# Current_Meas.net
KiCad netlist of a schematic drawn in Altium Designer
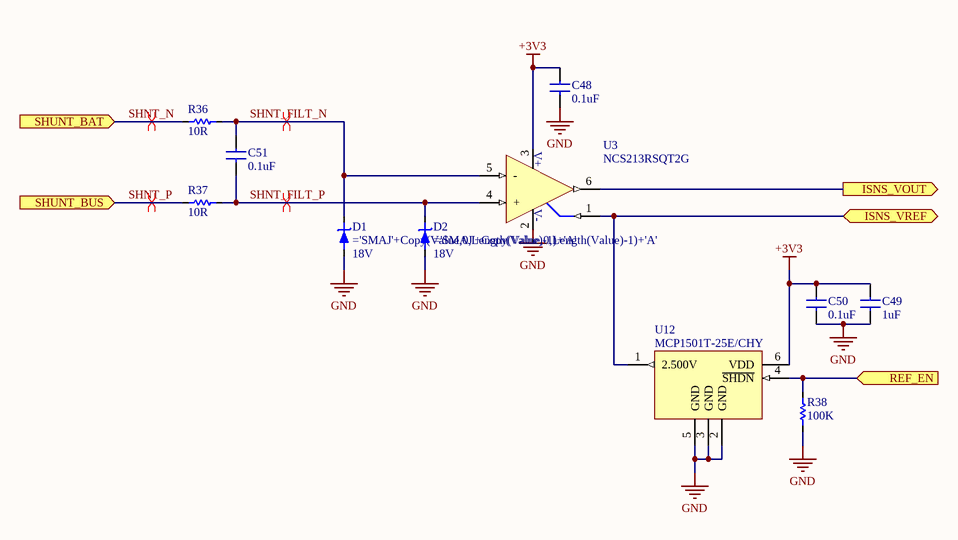
[diagram p0: Current_Meas.SchDoc]

(export (version "E")
  (design (tool "Eeschema 10.0.6"))
  (components
    (comp (ref "C48")
      (value "0.1uF")
      (footprint "0402_CAPACITOR")
      (description "CAP CERM 0.1uF 10% 16V 0402")
      (fields (field (name "VOLTAGE") "16V") (field (name "Comment") "CAP 0.1uF 16V X7R"))
      (libsource (lib "capacitor") (part "C_0402_0.1uF_16V_10%"))
    )
    (comp (ref "C49")
      (value "1uF")
      (footprint "0402_CAPACITOR")
      (description "CAP CERM 1uF 20% 6.3V 0402")
      (fields (field (name "VOLTAGE") "6.3V") (field (name "Comment") "CAP 1uF 6.3V X5R"))
      (libsource (lib "capacitor") (part "C_0402_1uF_6.3V_20%"))
    )
    (comp (ref "C50")
      (value "0.1uF")
      (footprint "0402_CAPACITOR")
      (description "CAP CERM 0.1uF 10% 16V 0402")
      (fields (field (name "VOLTAGE") "16V") (field (name "Comment") "CAP 0.1uF 16V X7R"))
      (libsource (lib "capacitor") (part "C_0402_0.1uF_16V_10%"))
    )
    (comp (ref "C51")
      (value "0.1uF")
      (footprint "0402_CAPACITOR")
      (description "CAP CERM 0.1uF 10% 16V 0402")
      (fields (field (name "VOLTAGE") "16V") (field (name "Comment") "CAP 0.1uF 16V X7R"))
      (libsource (lib "capacitor") (part "C_0402_0.1uF_16V_10%"))
    )
    (comp (ref "D1")
      (value "18V")
      (footprint "SMA")
      (description "SMA Unidirectional TVS Diode")
      (fields
        (field (name "MANUFACTURER") "Vishay")
        (field (name "MANUFACTURER PN") "SMAJA")
        (field (name "Comment") "TVS Diode")
      )
      (libsource (lib "diode") (part "D_TVS_SMAJ_Uni_generic"))
    )
    (comp (ref "D2")
      (value "18V")
      (footprint "SMA")
      (description "SMA Unidirectional TVS Diode")
      (fields
        (field (name "MANUFACTURER") "Vishay")
        (field (name "MANUFACTURER PN") "SMAJA")
        (field (name "Comment") "TVS Diode")
      )
      (libsource (lib "diode") (part "D_TVS_SMAJ_Uni_generic"))
    )
    (comp (ref "R36")
      (value "10R")
      (footprint "0402_Resistor")
      (description "Generic 0402 Resistor (10.2R to 10M)")
      (fields (field (name "TOLERANCE") "±1%") (field (name "MANUFACTURER") "Yageo"))
      (libsource (lib "resistor") (part "R_0402_generic_1%"))
    )
    (comp (ref "R37")
      (value "10R")
      (footprint "0402_Resistor")
      (description "Generic 0402 Resistor (10.2R to 10M)")
      (fields (field (name "TOLERANCE") "±1%") (field (name "MANUFACTURER") "Yageo"))
      (libsource (lib "resistor") (part "R_0402_generic_1%"))
    )
    (comp (ref "R38")
      (value "100K")
      (footprint "0402_Resistor")
      (description "Generic 0402 Resistor (10.2R to 10M)")
      (fields (field (name "TOLERANCE") "±1%") (field (name "MANUFACTURER") "Yageo"))
      (libsource (lib "resistor") (part "R_0402_generic_1%"))
    )
    (comp (ref "U3")
      (value "NCS213RSQT2G")
      (footprint "SC70-6")
      (description "Current Sense Amplifier 1 Circuit Rail-to-Rail SC-88/SC70-6/SOT-363, Gain=50")
      (fields (field (name "MANUFACTURER") "ON Semiconductor"))
      (libsource (lib "ic") (part "U_NCS213RSQT2G"))
    )
    (comp (ref "U12")
      (value "MCP1501T-25E/CHY")
      (footprint "SOT23-6")
      (description "Series Voltage Reference IC ±0.1% 20mA SOT-23-6")
      (fields (field (name "TOLERANCE") "0.1%") (field (name "MANUFACTURER") "Microchip"))
      (libsource (lib "ic") (part "U_MCP1501T-25E/CHY"))
    )
  )
  (nets
    (net (code "1") (name "+3V3") (class "Default")
      (node (ref "C48") (pin "1") (pinfunction "1_1") (pintype "passive"))
      (node (ref "C49") (pin "1") (pinfunction "1_1") (pintype "passive"))
      (node (ref "C50") (pin "1") (pinfunction "1_1") (pintype "passive"))
      (node (ref "U12") (pin "6") (pinfunction "VDD_6") (pintype "power_in"))
      (node (ref "U3") (pin "3") (pinfunction "VCC+_3") (pintype "power_in"))
    )
    (net (code "2") (name "/ISNS_VOUT") (class "Default")
      (node (ref "U3") (pin "6") (pinfunction "OUT_6") (pintype "output"))
    )
    (net (code "3") (name "/ISNS_VREF") (class "Default")
      (node (ref "U12") (pin "1") (pinfunction "2.500V_1") (pintype "output"))
      (node (ref "U3") (pin "1") (pinfunction "REF_1") (pintype "input"))
    )
    (net (code "4") (name "/REF_EN") (class "Default")
      (node (ref "R38") (pin "2") (pinfunction "2_2") (pintype "passive"))
      (node (ref "U12") (pin "4") (pinfunction "~{SHDN}_4") (pintype "input"))
    )
    (net (code "5") (name "/SHNT_FILT_N") (class "Default")
      (node (ref "C51") (pin "1") (pinfunction "1_1") (pintype "passive"))
      (node (ref "D1") (pin "2") (pinfunction "Cathode_2") (pintype "passive"))
      (node (ref "R36") (pin "2") (pinfunction "2_2") (pintype "passive"))
      (node (ref "U3") (pin "5") (pinfunction "-_5") (pintype "input"))
    )
    (net (code "6") (name "/SHNT_FILT_P") (class "Default")
      (node (ref "C51") (pin "2") (pinfunction "2_2") (pintype "passive"))
      (node (ref "D2") (pin "2") (pinfunction "Cathode_2") (pintype "passive"))
      (node (ref "R37") (pin "2") (pinfunction "2_2") (pintype "passive"))
      (node (ref "U3") (pin "4") (pinfunction "+_4") (pintype "input"))
    )
    (net (code "7") (name "/SHNT_N") (class "Default")
      (node (ref "R36") (pin "1") (pinfunction "1_1") (pintype "passive"))
    )
    (net (code "8") (name "/SHNT_P") (class "Default")
      (node (ref "R37") (pin "1") (pinfunction "1_1") (pintype "passive"))
    )
    (net (code "9") (name "GND") (class "Default")
      (node (ref "C48") (pin "2") (pinfunction "2_2") (pintype "passive"))
      (node (ref "C49") (pin "2") (pinfunction "2_2") (pintype "passive"))
      (node (ref "C50") (pin "2") (pinfunction "2_2") (pintype "passive"))
      (node (ref "D1") (pin "1") (pinfunction "Anode_1") (pintype "passive"))
      (node (ref "D2") (pin "1") (pinfunction "Anode_1") (pintype "passive"))
      (node (ref "R38") (pin "1") (pinfunction "1_1") (pintype "passive"))
      (node (ref "U12") (pin "2") (pinfunction "GND_2") (pintype "power_in"))
      (node (ref "U12") (pin "3") (pinfunction "GND_3") (pintype "power_in"))
      (node (ref "U12") (pin "5") (pinfunction "GND_5") (pintype "power_in"))
      (node (ref "U3") (pin "2") (pinfunction "VCC-_2") (pintype "power_in"))
    )
  )
)
